# PWM_Drivers.net
KiCad netlist of a schematic drawn in Altium Designer
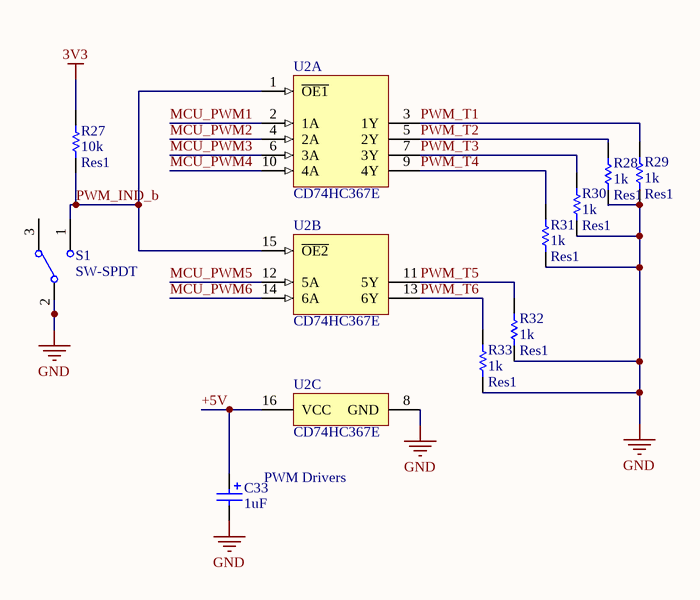
[diagram p0: PWM Drivers.SchDoc]

(export (version "E")
  (design (tool "Eeschema 10.0.6"))
  (components
    (comp (ref "C33")
      (value "1uF")
      (footprint "RAD-0.1")
      (description "Polarized Capacitor (Radial)")
      (fields (field (name "Comment") "Cap No Pol") (field (name "PUBLISHER") "Altium Limited"))
      (libsource (lib "LABSTEPS_Project") (part "Cap No Pol"))
    )
    (comp (ref "R27")
      (value "Res1")
      (footprint "AXIAL-0.4")
      (description "Resistor")
      (fields (field (name "ALTIUM_VALUE") "10k") (field (name "PUBLISHER") "Altium Limited"))
      (libsource (lib "Miscellaneous Devices") (part "Res1"))
    )
    (comp (ref "R28")
      (value "Res1")
      (footprint "AXIAL-0.4")
      (description "Resistor")
      (fields (field (name "ALTIUM_VALUE") "1k") (field (name "PUBLISHER") "Altium Limited"))
      (libsource (lib "Miscellaneous Devices") (part "Res1"))
    )
    (comp (ref "R29")
      (value "Res1")
      (footprint "AXIAL-0.4")
      (description "Resistor")
      (fields (field (name "ALTIUM_VALUE") "1k") (field (name "PUBLISHER") "Altium Limited"))
      (libsource (lib "Miscellaneous Devices") (part "Res1"))
    )
    (comp (ref "R30")
      (value "Res1")
      (footprint "AXIAL-0.4")
      (description "Resistor")
      (fields (field (name "ALTIUM_VALUE") "1k") (field (name "PUBLISHER") "Altium Limited"))
      (libsource (lib "Miscellaneous Devices") (part "Res1"))
    )
    (comp (ref "R31")
      (value "Res1")
      (footprint "AXIAL-0.4")
      (description "Resistor")
      (fields (field (name "ALTIUM_VALUE") "1k") (field (name "PUBLISHER") "Altium Limited"))
      (libsource (lib "Miscellaneous Devices") (part "Res1"))
    )
    (comp (ref "R32")
      (value "Res1")
      (footprint "AXIAL-0.4")
      (description "Resistor")
      (fields (field (name "ALTIUM_VALUE") "1k") (field (name "PUBLISHER") "Altium Limited"))
      (libsource (lib "Miscellaneous Devices") (part "Res1"))
    )
    (comp (ref "R33")
      (value "Res1")
      (footprint "AXIAL-0.4")
      (description "Resistor")
      (fields (field (name "ALTIUM_VALUE") "1k") (field (name "PUBLISHER") "Altium Limited"))
      (libsource (lib "Miscellaneous Devices") (part "Res1"))
    )
    (comp (ref "S1")
      (value "SW-SPDT")
      (footprint "MHDR1X3")
      (description "SPDT Subminiature Toggle Switch, Right Angle Mounting, Vertical Actuation")
      (fields (field (name "PUBLISHER") "Altium Limited"))
      (libsource (lib "LABSTEPS_Project") (part "SW-SPDT"))
    )
    (comp (ref "U2")
      (value "CD74HC367E")
      (footprint "N0016A")
      (description "High Speed CMOS Logic Hex Buffers/Line Drivers with Non-Inverting 3-State Outputs, N0016A, TUBE")
      (fields
        (field (name "GENERIC PART NUMBER") "CD74HC367")
        (field (name "MANUFACTURER") "Texas Instruments")
      )
      (libsource (lib "Altium Content Vault") (part "TI-CD74HC367-N0016A-16"))
    )
  )
  (nets
    (net (code "1") (name "/+5V") (class "Default")
      (node (ref "C33") (pin "1") (pinfunction "1_1") (pintype "passive"))
      (node (ref "U2") (pin "16") (pinfunction "VCC_16") (pintype "power_in"))
    )
    (net (code "2") (name "/MCU_PWM1") (class "Default")
      (node (ref "U2") (pin "2") (pinfunction "1A_2") (pintype "input"))
    )
    (net (code "3") (name "/MCU_PWM2") (class "Default")
      (node (ref "U2") (pin "4") (pinfunction "2A_4") (pintype "input"))
    )
    (net (code "4") (name "/MCU_PWM3") (class "Default")
      (node (ref "U2") (pin "6") (pinfunction "3A_6") (pintype "input"))
    )
    (net (code "5") (name "/MCU_PWM4") (class "Default")
      (node (ref "U2") (pin "10") (pinfunction "4A_10") (pintype "input"))
    )
    (net (code "6") (name "/MCU_PWM5") (class "Default")
      (node (ref "U2") (pin "12") (pinfunction "5A_12") (pintype "input"))
    )
    (net (code "7") (name "/MCU_PWM6") (class "Default")
      (node (ref "U2") (pin "14") (pinfunction "6A_14") (pintype "input"))
    )
    (net (code "8") (name "/PWM_IND_b") (class "Default")
      (node (ref "R27") (pin "1") (pinfunction "1_1") (pintype "passive"))
      (node (ref "S1") (pin "1") (pinfunction "1_1") (pintype "passive"))
      (node (ref "U2") (pin "1") (pinfunction "~{OE1}_1") (pintype "input"))
      (node (ref "U2") (pin "15") (pinfunction "~{OE2}_15") (pintype "input"))
    )
    (net (code "9") (name "/PWM_T1") (class "Default")
      (node (ref "R29") (pin "2") (pinfunction "2_2") (pintype "passive"))
      (node (ref "U2") (pin "3") (pinfunction "1Y_3") (pintype "tri_state"))
    )
    (net (code "10") (name "/PWM_T2") (class "Default")
      (node (ref "R28") (pin "2") (pinfunction "2_2") (pintype "passive"))
      (node (ref "U2") (pin "5") (pinfunction "2Y_5") (pintype "tri_state"))
    )
    (net (code "11") (name "/PWM_T3") (class "Default")
      (node (ref "R30") (pin "2") (pinfunction "2_2") (pintype "passive"))
      (node (ref "U2") (pin "7") (pinfunction "3Y_7") (pintype "tri_state"))
    )
    (net (code "12") (name "/PWM_T4") (class "Default")
      (node (ref "R31") (pin "2") (pinfunction "2_2") (pintype "passive"))
      (node (ref "U2") (pin "9") (pinfunction "4Y_9") (pintype "tri_state"))
    )
    (net (code "13") (name "/PWM_T5") (class "Default")
      (node (ref "R32") (pin "2") (pinfunction "2_2") (pintype "passive"))
      (node (ref "U2") (pin "11") (pinfunction "5Y_11") (pintype "tri_state"))
    )
    (net (code "14") (name "/PWM_T6") (class "Default")
      (node (ref "R33") (pin "2") (pinfunction "2_2") (pintype "passive"))
      (node (ref "U2") (pin "13") (pinfunction "6Y_13") (pintype "tri_state"))
    )
    (net (code "15") (name "3V3") (class "Default")
      (node (ref "R27") (pin "2") (pinfunction "2_2") (pintype "passive"))
    )
    (net (code "16") (name "GND") (class "Default")
      (node (ref "C33") (pin "2") (pinfunction "2_2") (pintype "passive"))
      (node (ref "R28") (pin "1") (pinfunction "1_1") (pintype "passive"))
      (node (ref "R29") (pin "1") (pinfunction "1_1") (pintype "passive"))
      (node (ref "R30") (pin "1") (pinfunction "1_1") (pintype "passive"))
      (node (ref "R31") (pin "1") (pinfunction "1_1") (pintype "passive"))
      (node (ref "R32") (pin "1") (pinfunction "1_1") (pintype "passive"))
      (node (ref "R33") (pin "1") (pinfunction "1_1") (pintype "passive"))
      (node (ref "S1") (pin "2") (pinfunction "2_2") (pintype "passive"))
      (node (ref "U2") (pin "8") (pinfunction "GND_8") (pintype "power_in"))
    )
    (net (code "17") (name "unconnected-(S1-Pad3)") (class "Default")
      (node (ref "S1") (pin "3") (pinfunction "3_3") (pintype "passive"))
    )
  )
)
